# DA1.net
KiCad netlist of a schematic drawn in Altium Designer
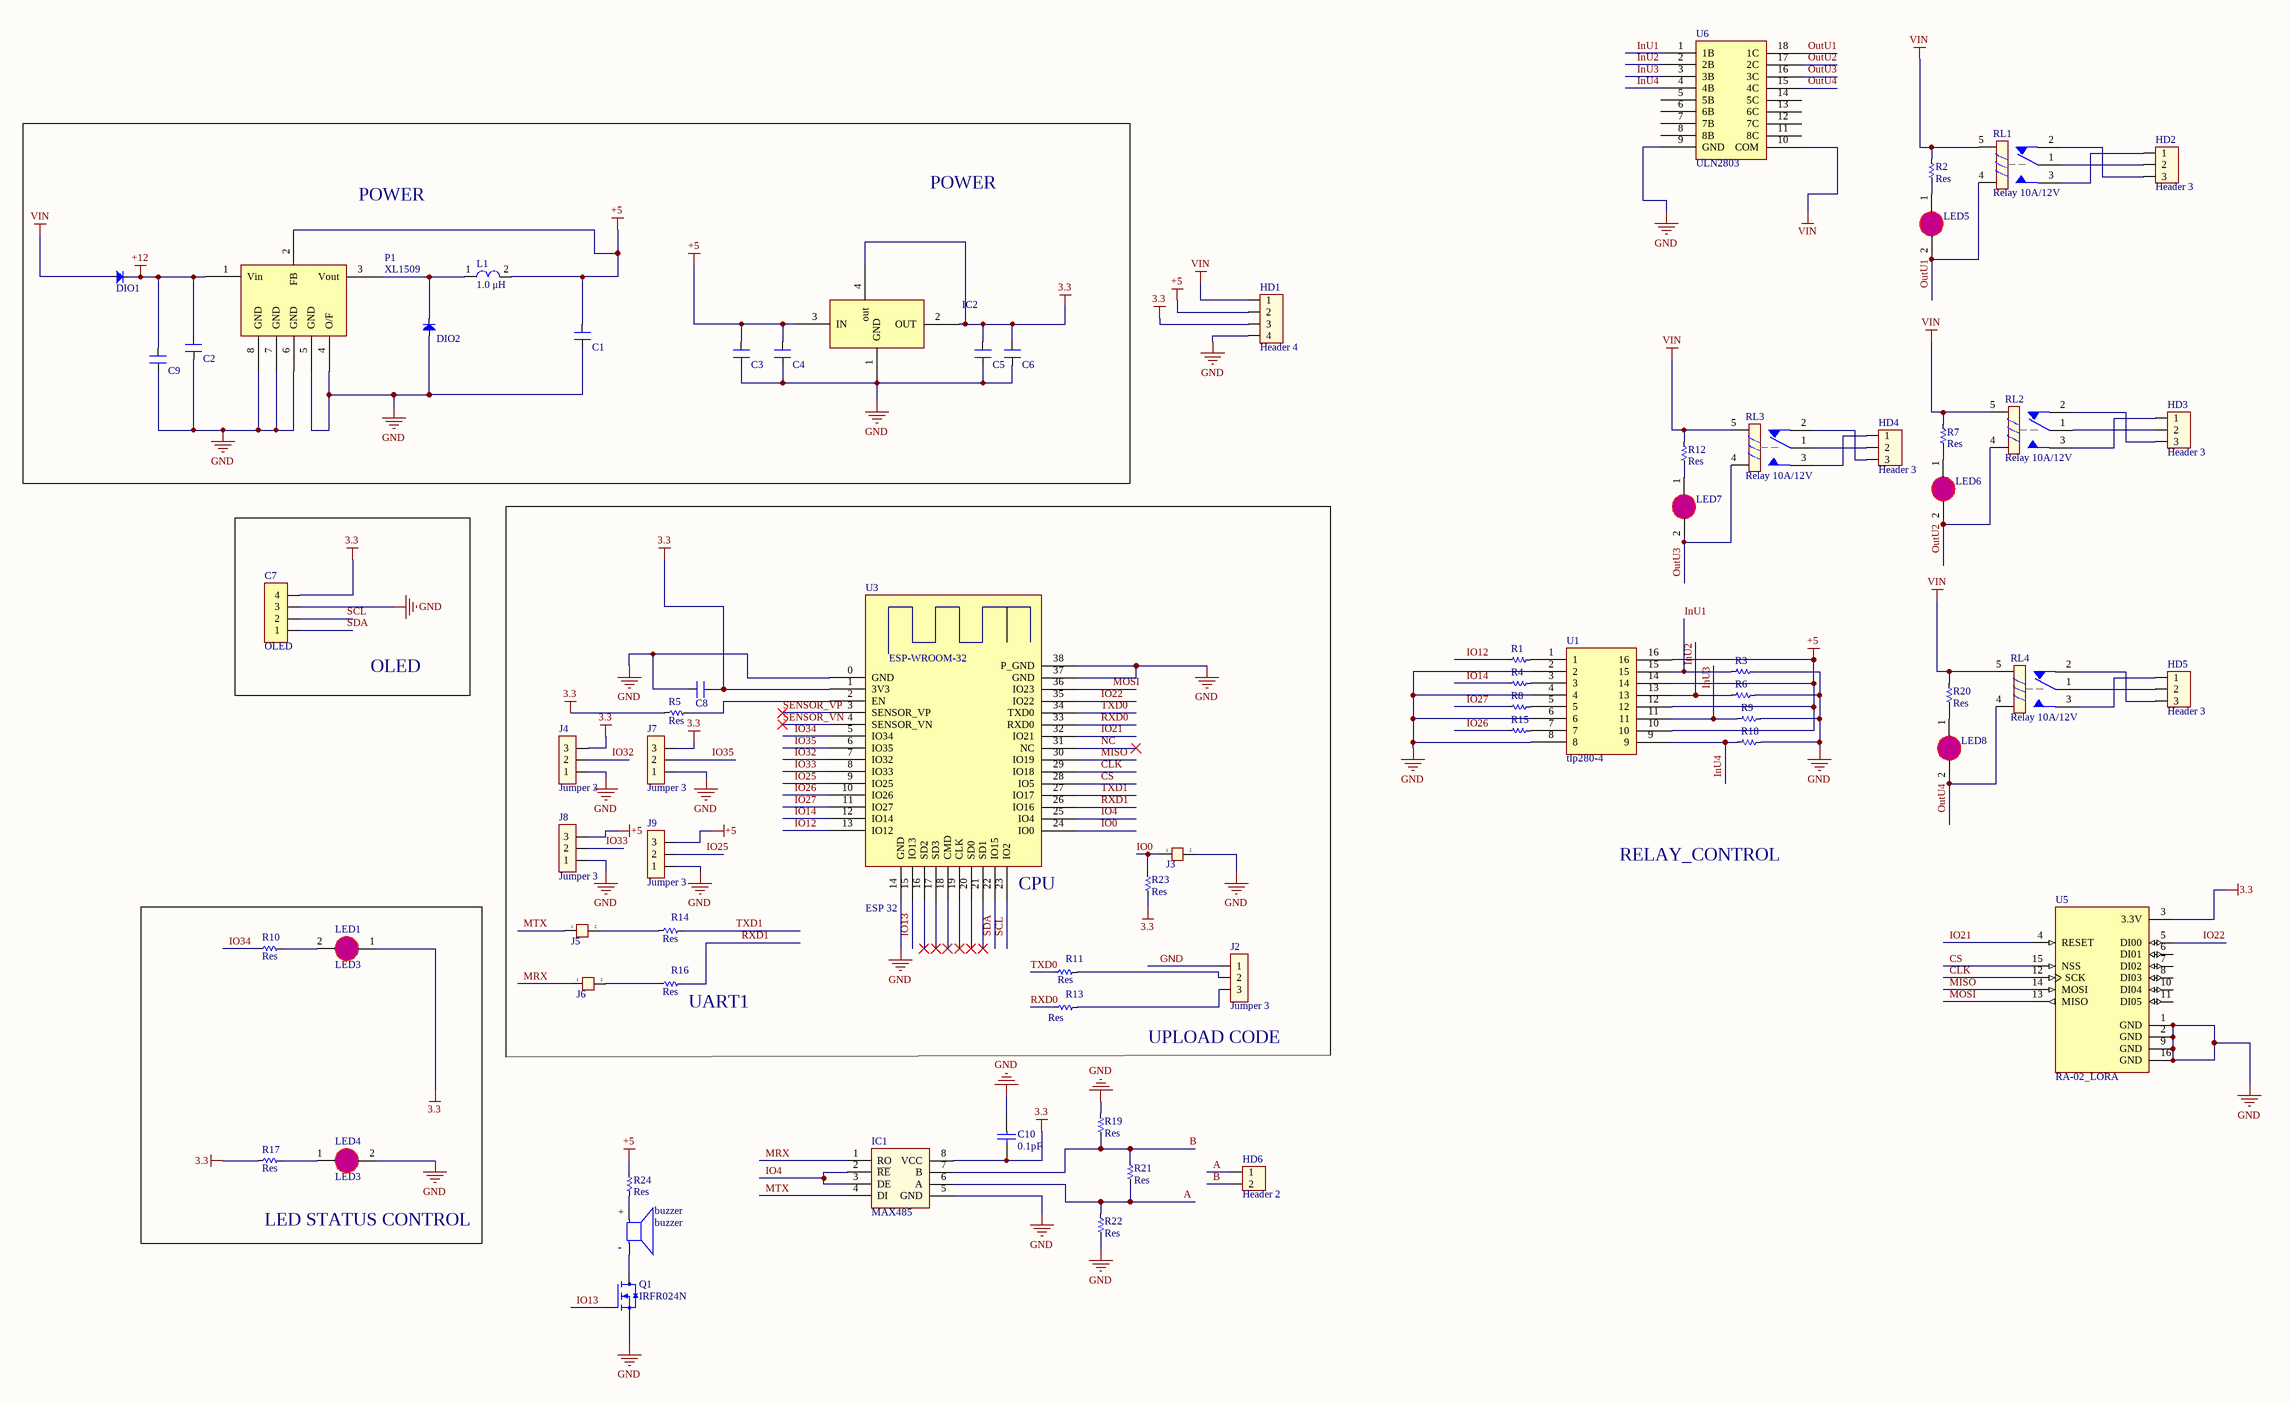
[diagram p0: DA1.SchDoc]

(export (version "E")
  (design (tool "Eeschema 10.0.6"))
  (components
    (comp (ref "buzzer")
      (value "buzzer")
      (footprint "buzzer")
      (description "ELECTRO-MECHANICAL AUDIO INDICATOR")
      (fields (field (name "MP") "AI-1223-TWT-12V-R") (field (name "MF") "PUI Audio,"))
      (libsource (lib "masterq") (part "buzzer"))
    )
    (comp (ref "C1")
      (value "CAPSMD")
      (footprint "1206")
      (description "Cap SMD")
      (libsource (lib "masterq") (part "CAPSMD"))
    )
    (comp (ref "C2")
      (value "CAPSMD")
      (footprint "1206")
      (description "Cap SMD")
      (libsource (lib "masterq") (part "CAPSMD"))
    )
    (comp (ref "C3")
      (value "CAPSMD")
      (footprint "SM-0805")
      (description "Cap SMD")
      (libsource (lib "masterq") (part "CAPSMD"))
    )
    (comp (ref "C4")
      (value "CAPSMD")
      (footprint "SM-0805")
      (description "Cap SMD")
      (libsource (lib "masterq") (part "CAPSMD"))
    )
    (comp (ref "C5")
      (value "CAPSMD")
      (footprint "SM-0805")
      (description "Cap SMD")
      (libsource (lib "masterq") (part "CAPSMD"))
    )
    (comp (ref "C6")
      (value "CAPSMD")
      (footprint "SM-0805")
      (description "Cap SMD")
      (libsource (lib "masterq") (part "CAPSMD"))
    )
    (comp (ref "C7")
      (value "OLED")
      (footprint "JP4-C1T")
      (description "WR-PHD 2.54 mm Angled Socket Header")
      (fields
        (field (name "MANUFACTURER") "Würth Elektronik eiSos GmbH")
        (field (name "PARTNO") "613004143121")
        (field (name "CREATED BY") "Karrer Zheng")
      )
      (libsource (lib "masterq") (part "JP4"))
    )
    (comp (ref "C8")
      (value "CAPSMD")
      (footprint "SM-0805")
      (description "Cap SMD")
      (libsource (lib "masterq") (part "CAPSMD"))
    )
    (comp (ref "C9")
      (value "CAPSMD")
      (footprint "1206")
      (description "Cap SMD")
      (libsource (lib "masterq") (part "CAPSMD"))
    )
    (comp (ref "C10")
      (value "0.1pF")
      (footprint "SMT0603")
      (description "CAP SM 0603 NC")
      (fields (field (name "TOLERANCE") "±10%") (field (name "Comment") "Cap"))
      (libsource (lib "masterq") (part "CAP-SM-0603-NC"))
    )
    (comp (ref "DIO1")
      (value "Diode SMD")
      (footprint "DIO-SMD-106")
      (description "Default Diode")
      (fields (field (name "PUBLISHER") "Altium Limited"))
      (libsource (lib "masterq") (part "Diode SMD"))
    )
    (comp (ref "DIO2")
      (value "Diode SMD")
      (footprint "DIO-SMD-106")
      (description "Default Diode")
      (fields (field (name "PUBLISHER") "Altium Limited"))
      (libsource (lib "masterq") (part "Diode SMD"))
    )
    (comp (ref "HD1")
      (value "Header 4")
      (footprint "HED4T")
      (description "Header 4 (Green)")
      (libsource (lib "masterq") (part "Hed4"))
    )
    (comp (ref "HD2")
      (value "Header 3")
      (footprint "HED3T")
      (description "Header 3 (Green)")
      (libsource (lib "masterq") (part "Hed3"))
    )
    (comp (ref "HD3")
      (value "Header 3")
      (footprint "HED3T")
      (description "Header 3 (Green)")
      (libsource (lib "masterq") (part "Hed3"))
    )
    (comp (ref "HD4")
      (value "Header 3")
      (footprint "HED3T")
      (description "Header 3 (Green)")
      (libsource (lib "masterq") (part "Hed3"))
    )
    (comp (ref "HD5")
      (value "Header 3")
      (footprint "HED3T")
      (description "Header 3 (Green)")
      (libsource (lib "masterq") (part "Hed3"))
    )
    (comp (ref "HD6")
      (value "Header 2")
      (footprint "HED2T")
      (description "Header 2 (Green)")
      (libsource (lib "masterq") (part "Hed2"))
    )
    (comp (ref "IC1")
      (value "MAX485")
      (footprint "SO-8")
      (description "RS232 - RS485 (Same sn75176)")
      (libsource (lib "masterq") (part "MAX485"))
    )
    (comp (ref "IC2")
      (value "ams1117")
      (footprint "SOT223-4N")
      (description "AMS 1117 : output 3.3,5,... (SOT223-4P)")
      (libsource (lib "masterq") (part "ams1117"))
    )
    (comp (ref "J2") (value "Jumper 3") (footprint "JP3") (libsource (lib "masterq") (part "JP3")))
    (comp (ref "J3") (value "Jumper 2") (footprint "J2") (libsource (lib "masterq") (part "JP 2")))
    (comp (ref "J4") (value "Jumper 3") (footprint "JP3") (libsource (lib "") (part "JP3_1")))
    (comp (ref "J5") (value "Jumper 2") (footprint "J2") (libsource (lib "masterq") (part "JP 2")))
    (comp (ref "J6") (value "Jumper 2") (footprint "J2") (libsource (lib "masterq") (part "JP 2")))
    (comp (ref "J7") (value "Jumper 3") (footprint "JP3") (libsource (lib "") (part "JP3_1")))
    (comp (ref "J8") (value "Jumper 3") (footprint "JP3") (libsource (lib "") (part "JP3_1")))
    (comp (ref "J9") (value "Jumper 3") (footprint "JP3") (libsource (lib "") (part "JP3_1")))
    (comp (ref "L1")
      (value "1.0 μH")
      (footprint "L-SMD-M-7.3x4.5")
      (fields
        (field (name "PARTNO") "78477010")
        (field (name "MANUFACTURER") "Wurth Elektronik")
        (field (name "CREATED BY") "Baojun Chen")
      )
      (libsource (lib "masterq") (part "L-SMD-1"))
    )
    (comp (ref "LED1")
      (value "LED3")
      (footprint "LED0805")
      (description "LED 3mm")
      (libsource (lib "masterq") (part "LEDSMD"))
    )
    (comp (ref "LED4")
      (value "LED3")
      (footprint "LED0805")
      (description "LED 3mm")
      (libsource (lib "masterq") (part "LEDSMD"))
    )
    (comp (ref "LED5")
      (value "~")
      (footprint "LED0805")
      (description "LED 3mm")
      (libsource (lib "masterq") (part "LEDSMD"))
    )
    (comp (ref "LED6")
      (value "~")
      (footprint "LED0805")
      (description "LED 3mm")
      (libsource (lib "masterq") (part "LEDSMD"))
    )
    (comp (ref "LED7")
      (value "~")
      (footprint "LED0805")
      (description "LED 3mm")
      (libsource (lib "masterq") (part "LEDSMD"))
    )
    (comp (ref "LED8")
      (value "~")
      (footprint "LED0805")
      (description "LED 3mm")
      (libsource (lib "masterq") (part "LEDSMD"))
    )
    (comp (ref "P1") (value "XL1509") (footprint "SOIC-8") (libsource (lib "masterq") (part "XL1509")))
    (comp (ref "Q1")
      (value "IRFR024N")
      (footprint "FET-SMD")
      (description "N-Channel 55 V 17A (Tc) 45W (Tc) Surface Mount D-Pak")
      (fields (field (name "MF") "Infineon Technologies"))
      (libsource (lib "masterq") (part "IRFR024N"))
    )
    (comp (ref "R1")
      (value "Res")
      (footprint "RES-SMD-0805")
      (description "Resistor")
      (fields
        (field (name "MANUFACTURER") "Generic Components")
        (field (name "PUBLISHER") "Altium Hobart Technology Centre")
      )
      (libsource (lib "masterq") (part "Res-SMD"))
    )
    (comp (ref "R2")
      (value "Res")
      (footprint "RES-SMD-0805")
      (description "Resistor")
      (fields
        (field (name "MANUFACTURER") "Generic Components")
        (field (name "PUBLISHER") "Altium Hobart Technology Centre")
      )
      (libsource (lib "masterq") (part "Res-SMD"))
    )
    (comp (ref "R3")
      (value "Res")
      (footprint "RES-SMD-0805")
      (description "Resistor")
      (fields
        (field (name "MANUFACTURER") "Generic Components")
        (field (name "PUBLISHER") "Altium Hobart Technology Centre")
      )
      (libsource (lib "masterq") (part "Res-SMD"))
    )
    (comp (ref "R4")
      (value "Res")
      (footprint "RES-SMD-0805")
      (description "Resistor")
      (fields
        (field (name "MANUFACTURER") "Generic Components")
        (field (name "PUBLISHER") "Altium Hobart Technology Centre")
      )
      (libsource (lib "masterq") (part "Res-SMD"))
    )
    (comp (ref "R5")
      (value "Res")
      (footprint "RES-SMD-0805")
      (description "Resistor")
      (fields
        (field (name "MANUFACTURER") "Generic Components")
        (field (name "PUBLISHER") "Altium Hobart Technology Centre")
      )
      (libsource (lib "masterq") (part "Res-SMD"))
    )
    (comp (ref "R6")
      (value "Res")
      (footprint "RES-SMD-0805")
      (description "Resistor")
      (fields
        (field (name "MANUFACTURER") "Generic Components")
        (field (name "PUBLISHER") "Altium Hobart Technology Centre")
      )
      (libsource (lib "masterq") (part "Res-SMD"))
    )
    (comp (ref "R7")
      (value "Res")
      (footprint "RES-SMD-0805")
      (description "Resistor")
      (fields
        (field (name "MANUFACTURER") "Generic Components")
        (field (name "PUBLISHER") "Altium Hobart Technology Centre")
      )
      (libsource (lib "masterq") (part "Res-SMD"))
    )
    (comp (ref "R8")
      (value "Res")
      (footprint "RES-SMD-0805")
      (description "Resistor")
      (fields
        (field (name "MANUFACTURER") "Generic Components")
        (field (name "PUBLISHER") "Altium Hobart Technology Centre")
      )
      (libsource (lib "masterq") (part "Res-SMD"))
    )
    (comp (ref "R9")
      (value "Res")
      (footprint "RES-SMD-0805")
      (description "Resistor")
      (fields
        (field (name "MANUFACTURER") "Generic Components")
        (field (name "PUBLISHER") "Altium Hobart Technology Centre")
      )
      (libsource (lib "masterq") (part "Res-SMD"))
    )
    (comp (ref "R10")
      (value "Res")
      (footprint "RES-SMD-0805")
      (description "Resistor")
      (fields
        (field (name "MANUFACTURER") "Generic Components")
        (field (name "PUBLISHER") "Altium Hobart Technology Centre")
      )
      (libsource (lib "masterq") (part "Res-SMD"))
    )
    (comp (ref "R11")
      (value "Res")
      (footprint "RES-SMD-0805")
      (description "Resistor")
      (fields
        (field (name "MANUFACTURER") "Generic Components")
        (field (name "PUBLISHER") "Altium Hobart Technology Centre")
      )
      (libsource (lib "masterq") (part "Res-SMD"))
    )
    (comp (ref "R12")
      (value "Res")
      (footprint "RES-SMD-0805")
      (description "Resistor")
      (fields
        (field (name "MANUFACTURER") "Generic Components")
        (field (name "PUBLISHER") "Altium Hobart Technology Centre")
      )
      (libsource (lib "masterq") (part "Res-SMD"))
    )
    (comp (ref "R13")
      (value "Res")
      (footprint "RES-SMD-0805")
      (description "Resistor")
      (fields
        (field (name "MANUFACTURER") "Generic Components")
        (field (name "PUBLISHER") "Altium Hobart Technology Centre")
      )
      (libsource (lib "masterq") (part "Res-SMD"))
    )
    (comp (ref "R14")
      (value "Res")
      (footprint "RES-SMD-0805")
      (description "Resistor")
      (fields
        (field (name "MANUFACTURER") "Generic Components")
        (field (name "PUBLISHER") "Altium Hobart Technology Centre")
      )
      (libsource (lib "masterq") (part "Res-SMD"))
    )
    (comp (ref "R15")
      (value "Res")
      (footprint "RES-SMD-0805")
      (description "Resistor")
      (fields
        (field (name "MANUFACTURER") "Generic Components")
        (field (name "PUBLISHER") "Altium Hobart Technology Centre")
      )
      (libsource (lib "masterq") (part "Res-SMD"))
    )
    (comp (ref "R16")
      (value "Res")
      (footprint "RES-SMD-0805")
      (description "Resistor")
      (fields
        (field (name "MANUFACTURER") "Generic Components")
        (field (name "PUBLISHER") "Altium Hobart Technology Centre")
      )
      (libsource (lib "masterq") (part "Res-SMD"))
    )
    (comp (ref "R17")
      (value "Res")
      (footprint "RES-SMD-0805")
      (description "Resistor")
      (fields
        (field (name "MANUFACTURER") "Generic Components")
        (field (name "PUBLISHER") "Altium Hobart Technology Centre")
      )
      (libsource (lib "masterq") (part "Res-SMD"))
    )
    (comp (ref "R18")
      (value "Res")
      (footprint "RES-SMD-0805")
      (description "Resistor")
      (fields
        (field (name "MANUFACTURER") "Generic Components")
        (field (name "PUBLISHER") "Altium Hobart Technology Centre")
      )
      (libsource (lib "masterq") (part "Res-SMD"))
    )
    (comp (ref "R19")
      (value "Res")
      (footprint "RES-SMD-0805")
      (description "Resistor")
      (fields
        (field (name "MANUFACTURER") "Generic Components")
        (field (name "PUBLISHER") "Altium Hobart Technology Centre")
      )
      (libsource (lib "masterq") (part "Res-SMD"))
    )
    (comp (ref "R20")
      (value "Res")
      (footprint "RES-SMD-0805")
      (description "Resistor")
      (fields
        (field (name "MANUFACTURER") "Generic Components")
        (field (name "PUBLISHER") "Altium Hobart Technology Centre")
      )
      (libsource (lib "masterq") (part "Res-SMD"))
    )
    (comp (ref "R21")
      (value "Res")
      (footprint "RES-SMD-0805")
      (description "Resistor")
      (fields
        (field (name "MANUFACTURER") "Generic Components")
        (field (name "PUBLISHER") "Altium Hobart Technology Centre")
      )
      (libsource (lib "masterq") (part "Res-SMD"))
    )
    (comp (ref "R22")
      (value "Res")
      (footprint "RES-SMD-0805")
      (description "Resistor")
      (fields
        (field (name "MANUFACTURER") "Generic Components")
        (field (name "PUBLISHER") "Altium Hobart Technology Centre")
      )
      (libsource (lib "masterq") (part "Res-SMD"))
    )
    (comp (ref "R23")
      (value "Res")
      (footprint "RES-SMD-0805")
      (description "Resistor")
      (fields
        (field (name "MANUFACTURER") "Generic Components")
        (field (name "PUBLISHER") "Altium Hobart Technology Centre")
      )
      (libsource (lib "masterq") (part "Res-SMD"))
    )
    (comp (ref "R24")
      (value "Res")
      (footprint "RES-SMD-0805")
      (description "Resistor")
      (fields
        (field (name "MANUFACTURER") "Generic Components")
        (field (name "PUBLISHER") "Altium Hobart Technology Centre")
      )
      (libsource (lib "masterq") (part "Res-SMD"))
    )
    (comp (ref "RL1")
      (value "Relay 10A/12V")
      (footprint "RL_SPDT_10A")
      (description "Relay SPDT,10A - 12VDC 5 Pin")
      (libsource (lib "masterq") (part "Relay 1_1"))
    )
    (comp (ref "RL2")
      (value "Relay 10A/12V")
      (footprint "RL_SPDT_10A")
      (description "Relay SPDT,10A - 12VDC 5 Pin")
      (libsource (lib "masterq") (part "Relay 1_1"))
    )
    (comp (ref "RL3")
      (value "Relay 10A/12V")
      (footprint "RL_SPDT_10A")
      (description "Relay SPDT,10A - 12VDC 5 Pin")
      (libsource (lib "masterq") (part "Relay 1_1"))
    )
    (comp (ref "RL4")
      (value "Relay 10A/12V")
      (footprint "RL_SPDT_10A")
      (description "Relay SPDT,10A - 12VDC 5 Pin")
      (libsource (lib "masterq") (part "Relay 1_1"))
    )
    (comp (ref "U1") (value "tlp280-4") (footprint "SOP16") (libsource (lib "masterq") (part "tlp280-4")))
    (comp (ref "U3") (value "ESP 32") (footprint "ESP 32") (libsource (lib "masterq") (part "ESP 32")))
    (comp (ref "U5")
      (value "RA-02_LORA")
      (footprint "MODULE_RA-02_LORA")
      (description "Ra-02 LoRa RF M5Stack Platform Evaluation Expansion Board")
      (fields (field (name "MP") "Ra-02 LoRa") (field (name "MF") "AI-Thinker"))
      (libsource (lib "masterq") (part "RA-02_LORA"))
    )
    (comp (ref "U6")
      (value "ULN2803")
      (footprint "SOIC 18")
      (description "Darlington Transistor Arrays")
      (libsource (lib "masterq") (part "ULN2803_1"))
    )
  )
  (nets
    (net (code "1") (name "+5") (class "Default")
      (node (ref "C1") (pin "2") (pinfunction "2_2") (pintype "passive"))
      (node (ref "C3") (pin "2") (pinfunction "2_2") (pintype "passive"))
      (node (ref "C4") (pin "2") (pinfunction "2_2") (pintype "passive"))
      (node (ref "HD1") (pin "2") (pinfunction "2_2") (pintype "passive"))
      (node (ref "IC2") (pin "3") (pinfunction "IN_3") (pintype "passive"))
      (node (ref "J8") (pin "3") (pinfunction "3_3") (pintype "passive"))
      (node (ref "J9") (pin "3") (pinfunction "3_3") (pintype "passive"))
      (node (ref "L1") (pin "2") (pinfunction "2_2") (pintype "passive"))
      (node (ref "P1") (pin "2") (pinfunction "FB_2") (pintype "passive"))
      (node (ref "R24") (pin "1") (pinfunction "1_1") (pintype "passive"))
      (node (ref "U1") (pin "10") (pinfunction "10_10") (pintype "passive"))
      (node (ref "U1") (pin "12") (pinfunction "12_12") (pintype "passive"))
      (node (ref "U1") (pin "14") (pinfunction "14_14") (pintype "passive"))
      (node (ref "U1") (pin "16") (pinfunction "16_16") (pintype "passive"))
    )
    (net (code "2") (name "+12") (class "Default")
      (node (ref "C2") (pin "2") (pinfunction "2_2") (pintype "passive"))
      (node (ref "C9") (pin "2") (pinfunction "2_2") (pintype "passive"))
      (node (ref "DIO1") (pin "2") (pinfunction "K_2") (pintype "passive"))
      (node (ref "P1") (pin "1") (pinfunction "Vin_1") (pintype "passive"))
    )
    (net (code "3") (name "/A") (class "Default")
      (node (ref "HD6") (pin "1") (pinfunction "1_1") (pintype "passive"))
      (node (ref "IC1") (pin "6") (pinfunction "A_6") (pintype "passive"))
      (node (ref "R21") (pin "2") (pinfunction "2_2") (pintype "passive"))
      (node (ref "R22") (pin "1") (pinfunction "1_1") (pintype "passive"))
    )
    (net (code "4") (name "/B") (class "Default")
      (node (ref "HD6") (pin "2") (pinfunction "2_2") (pintype "passive"))
      (node (ref "IC1") (pin "7") (pinfunction "B_7") (pintype "passive"))
      (node (ref "R19") (pin "2") (pinfunction "2_2") (pintype "passive"))
      (node (ref "R21") (pin "1") (pinfunction "1_1") (pintype "passive"))
    )
    (net (code "5") (name "/CLK") (class "Default")
      (node (ref "U3") (pin "29") (pinfunction "IO18_29") (pintype "passive"))
      (node (ref "U5") (pin "12") (pinfunction "SCK_12") (pintype "input"))
    )
    (net (code "6") (name "/CS") (class "Default")
      (node (ref "U3") (pin "28") (pinfunction "IO5_28") (pintype "passive"))
      (node (ref "U5") (pin "15") (pinfunction "NSS_15") (pintype "input"))
    )
    (net (code "7") (name "/IO0") (class "Default")
      (node (ref "J3") (pin "1") (pinfunction "1_1") (pintype "passive"))
      (node (ref "R23") (pin "1") (pinfunction "1_1") (pintype "passive"))
      (node (ref "U3") (pin "24") (pinfunction "IO0_24") (pintype "passive"))
    )
    (net (code "8") (name "/IO4") (class "Default")
      (node (ref "IC1") (pin "2") (pinfunction "~{RE}_2") (pintype "passive"))
      (node (ref "IC1") (pin "3") (pinfunction "DE_3") (pintype "passive"))
      (node (ref "U3") (pin "25") (pinfunction "IO4_25") (pintype "passive"))
    )
    (net (code "9") (name "/IO12") (class "Default")
      (node (ref "R1") (pin "1") (pinfunction "1_1") (pintype "passive"))
      (node (ref "U3") (pin "13") (pinfunction "IO12_13") (pintype "passive"))
    )
    (net (code "10") (name "/IO13") (class "Default")
      (node (ref "Q1") (pin "1") (pinfunction "G_1") (pintype "passive"))
      (node (ref "U3") (pin "15") (pinfunction "IO13_15") (pintype "passive"))
    )
    (net (code "11") (name "/IO14") (class "Default")
      (node (ref "R4") (pin "1") (pinfunction "1_1") (pintype "passive"))
      (node (ref "U3") (pin "12") (pinfunction "IO14_12") (pintype "passive"))
    )
    (net (code "12") (name "/IO21") (class "Default")
      (node (ref "U3") (pin "32") (pinfunction "IO21_32") (pintype "passive"))
      (node (ref "U5") (pin "4") (pinfunction "RESET_4") (pintype "input"))
    )
    (net (code "13") (name "/IO22") (class "Default")
      (node (ref "U3") (pin "35") (pinfunction "IO22_35") (pintype "passive"))
      (node (ref "U5") (pin "5") (pinfunction "DI00_5") (pintype "bidirectional"))
    )
    (net (code "14") (name "/IO25") (class "Default")
      (node (ref "J9") (pin "2") (pinfunction "2_2") (pintype "passive"))
      (node (ref "U3") (pin "9") (pinfunction "IO25_9") (pintype "passive"))
    )
    (net (code "15") (name "/IO26") (class "Default")
      (node (ref "R15") (pin "1") (pinfunction "1_1") (pintype "passive"))
      (node (ref "U3") (pin "10") (pinfunction "IO26_10") (pintype "passive"))
    )
    (net (code "16") (name "/IO27") (class "Default")
      (node (ref "R8") (pin "1") (pinfunction "1_1") (pintype "passive"))
      (node (ref "U3") (pin "11") (pinfunction "IO27_11") (pintype "passive"))
    )
    (net (code "17") (name "/IO32") (class "Default")
      (node (ref "J4") (pin "2") (pinfunction "2_2") (pintype "passive"))
      (node (ref "U3") (pin "7") (pinfunction "IO32_7") (pintype "passive"))
    )
    (net (code "18") (name "/IO33") (class "Default")
      (node (ref "J8") (pin "2") (pinfunction "2_2") (pintype "passive"))
      (node (ref "U3") (pin "8") (pinfunction "IO33_8") (pintype "passive"))
    )
    (net (code "19") (name "/IO34") (class "Default")
      (node (ref "R10") (pin "2") (pinfunction "2_2") (pintype "passive"))
      (node (ref "U3") (pin "5") (pinfunction "IO34_5") (pintype "passive"))
    )
    (net (code "20") (name "/IO35") (class "Default")
      (node (ref "J7") (pin "2") (pinfunction "2_2") (pintype "passive"))
      (node (ref "U3") (pin "6") (pinfunction "IO35_6") (pintype "passive"))
    )
    (net (code "21") (name "/InU1") (class "Default")
      (node (ref "R3") (pin "1") (pinfunction "1_1") (pintype "passive"))
      (node (ref "U1") (pin "15") (pinfunction "15_15") (pintype "passive"))
      (node (ref "U6") (pin "1") (pinfunction "1B_1") (pintype "passive"))
    )
    (net (code "22") (name "/InU2") (class "Default")
      (node (ref "R6") (pin "1") (pinfunction "1_1") (pintype "passive"))
      (node (ref "U1") (pin "13") (pinfunction "13_13") (pintype "passive"))
      (node (ref "U6") (pin "2") (pinfunction "2B_2") (pintype "passive"))
    )
    (net (code "23") (name "/InU3") (class "Default")
      (node (ref "R9") (pin "1") (pinfunction "1_1") (pintype "passive"))
      (node (ref "U1") (pin "11") (pinfunction "11_11") (pintype "passive"))
      (node (ref "U6") (pin "3") (pinfunction "3B_3") (pintype "passive"))
    )
    (net (code "24") (name "/InU4") (class "Default")
      (node (ref "R18") (pin "1") (pinfunction "1_1") (pintype "passive"))
      (node (ref "U1") (pin "9") (pinfunction "9_9") (pintype "passive"))
      (node (ref "U6") (pin "4") (pinfunction "4B_4") (pintype "passive"))
    )
    (net (code "25") (name "/MISO") (class "Default")
      (node (ref "U3") (pin "30") (pinfunction "IO19_30") (pintype "passive"))
      (node (ref "U5") (pin "14") (pinfunction "MOSI_14") (pintype "input"))
    )
    (net (code "26") (name "/MOSI") (class "Default")
      (node (ref "U3") (pin "36") (pinfunction "IO23_36") (pintype "passive"))
      (node (ref "U5") (pin "13") (pinfunction "MISO_13") (pintype "output"))
    )
    (net (code "27") (name "/MRX") (class "Default")
      (node (ref "IC1") (pin "1") (pinfunction "RO_1") (pintype "passive"))
      (node (ref "J6") (pin "1") (pinfunction "1_1") (pintype "passive"))
    )
    (net (code "28") (name "/MTX") (class "Default")
      (node (ref "IC1") (pin "4") (pinfunction "DI_4") (pintype "passive"))
      (node (ref "J5") (pin "1") (pinfunction "1_1") (pintype "passive"))
    )
    (net (code "29") (name "/NC") (class "Default")
      (node (ref "U3") (pin "31") (pinfunction "NC_31") (pintype "passive+no_connect"))
    )
    (net (code "30") (name "/OutU1") (class "Default")
      (node (ref "LED5") (pin "2") (pinfunction "K_2") (pintype "passive"))
      (node (ref "RL1") (pin "4") (pinfunction "4_4") (pintype "passive"))
      (node (ref "U6") (pin "18") (pinfunction "1C_18") (pintype "passive"))
    )
    (net (code "31") (name "/OutU2") (class "Default")
      (node (ref "LED6") (pin "2") (pinfunction "K_2") (pintype "passive"))
      (node (ref "RL2") (pin "4") (pinfunction "4_4") (pintype "passive"))
      (node (ref "U6") (pin "17") (pinfunction "2C_17") (pintype "passive"))
    )
    (net (code "32") (name "/OutU3") (class "Default")
      (node (ref "LED7") (pin "2") (pinfunction "K_2") (pintype "passive"))
      (node (ref "RL3") (pin "4") (pinfunction "4_4") (pintype "passive"))
      (node (ref "U6") (pin "16") (pinfunction "3C_16") (pintype "passive"))
    )
    (net (code "33") (name "/OutU4") (class "Default")
      (node (ref "LED8") (pin "2") (pinfunction "K_2") (pintype "passive"))
      (node (ref "RL4") (pin "4") (pinfunction "4_4") (pintype "passive"))
      (node (ref "U6") (pin "15") (pinfunction "4C_15") (pintype "passive"))
    )
    (net (code "34") (name "/RXD0") (class "Default")
      (node (ref "R13") (pin "2") (pinfunction "2_2") (pintype "passive"))
      (node (ref "U3") (pin "33") (pinfunction "RXD0_33") (pintype "passive"))
    )
    (net (code "35") (name "/RXD1") (class "Default")
      (node (ref "R16") (pin "1") (pinfunction "1_1") (pintype "passive"))
      (node (ref "U3") (pin "26") (pinfunction "IO16_26") (pintype "passive"))
    )
    (net (code "36") (name "/SCL") (class "Default")
      (node (ref "C7") (pin "2") (pinfunction "2_2") (pintype "passive"))
      (node (ref "U3") (pin "23") (pinfunction "IO2_23") (pintype "passive"))
    )
    (net (code "37") (name "/SDA") (class "Default")
      (node (ref "C7") (pin "1") (pinfunction "1_1") (pintype "passive"))
      (node (ref "U3") (pin "22") (pinfunction "IO15_22") (pintype "passive"))
    )
    (net (code "38") (name "/SENSOR_VN") (class "Default")
      (node (ref "U3") (pin "4") (pinfunction "SENSOR_VN_4") (pintype "passive+no_connect"))
    )
    (net (code "39") (name "/SENSOR_VP") (class "Default")
      (node (ref "U3") (pin "3") (pinfunction "SENSOR_VP_3") (pintype "passive+no_connect"))
    )
    (net (code "40") (name "/TXD0") (class "Default")
      (node (ref "R11") (pin "2") (pinfunction "2_2") (pintype "passive"))
      (node (ref "U3") (pin "34") (pinfunction "TXD0_34") (pintype "passive"))
    )
    (net (code "41") (name "/TXD1") (class "Default")
      (node (ref "R14") (pin "1") (pinfunction "1_1") (pintype "passive"))
      (node (ref "U3") (pin "27") (pinfunction "IO17_27") (pintype "passive"))
    )
    (net (code "42") (name "3.3") (class "Default")
      (node (ref "C10") (pin "1") (pinfunction "1_1") (pintype "passive"))
      (node (ref "C5") (pin "2") (pinfunction "2_2") (pintype "passive"))
      (node (ref "C6") (pin "2") (pinfunction "2_2") (pintype "passive"))
      (node (ref "C7") (pin "4") (pinfunction "4_4") (pintype "passive"))
      (node (ref "C8") (pin "2") (pinfunction "2_2") (pintype "passive"))
      (node (ref "HD1") (pin "3") (pinfunction "3_3") (pintype "passive"))
      (node (ref "IC1") (pin "8") (pinfunction "VCC_8") (pintype "passive"))
      (node (ref "IC2") (pin "2") (pinfunction "OUT_2") (pintype "passive"))
      (node (ref "IC2") (pin "4") (pinfunction "out_4") (pintype "passive"))
      (node (ref "J4") (pin "3") (pinfunction "3_3") (pintype "passive"))
      (node (ref "J7") (pin "3") (pinfunction "3_3") (pintype "passive"))
      (node (ref "LED1") (pin "1") (pinfunction "A_1") (pintype "passive"))
      (node (ref "R17") (pin "2") (pinfunction "2_2") (pintype "passive"))
      (node (ref "R23") (pin "2") (pinfunction "2_2") (pintype "passive"))
      (node (ref "R5") (pin "2") (pinfunction "2_2") (pintype "passive"))
      (node (ref "U3") (pin "1") (pinfunction "3V3_1") (pintype "passive"))
      (node (ref "U5") (pin "3") (pinfunction "3.3V_3") (pintype "power_in"))
    )
    (net (code "43") (name "GND") (class "Default")
      (node (ref "C1") (pin "1") (pinfunction "1_1") (pintype "passive"))
      (node (ref "C10") (pin "2") (pinfunction "2_2") (pintype "passive"))
      (node (ref "C2") (pin "1") (pinfunction "1_1") (pintype "passive"))
      (node (ref "C3") (pin "1") (pinfunction "1_1") (pintype "passive"))
      (node (ref "C4") (pin "1") (pinfunction "1_1") (pintype "passive"))
      (node (ref "C5") (pin "1") (pinfunction "1_1") (pintype "passive"))
      (node (ref "C6") (pin "1") (pinfunction "1_1") (pintype "passive"))
      (node (ref "C7") (pin "3") (pinfunction "3_3") (pintype "passive"))
      (node (ref "C8") (pin "1") (pinfunction "1_1") (pintype "passive"))
      (node (ref "C9") (pin "1") (pinfunction "1_1") (pintype "passive"))
      (node (ref "DIO2") (pin "1") (pinfunction "A_1") (pintype "passive"))
      (node (ref "HD1") (pin "4") (pinfunction "4_4") (pintype "passive"))
      (node (ref "IC1") (pin "5") (pinfunction "GND_5") (pintype "passive"))
      (node (ref "IC2") (pin "1") (pinfunction "GND_1") (pintype "passive"))
      (node (ref "J2") (pin "1") (pinfunction "1_1") (pintype "passive"))
      (node (ref "J3") (pin "2") (pinfunction "2_2") (pintype "passive"))
      (node (ref "J4") (pin "1") (pinfunction "1_1") (pintype "passive"))
      (node (ref "J7") (pin "1") (pinfunction "1_1") (pintype "passive"))
      (node (ref "J8") (pin "1") (pinfunction "1_1") (pintype "passive"))
      (node (ref "J9") (pin "1") (pinfunction "1_1") (pintype "passive"))
      (node (ref "LED4") (pin "2") (pinfunction "K_2") (pintype "passive"))
      (node (ref "P1") (pin "4") (pinfunction "O/F_4") (pintype "passive"))
      (node (ref "P1") (pin "5") (pinfunction "GND_5") (pintype "passive"))
      (node (ref "P1") (pin "6") (pinfunction "GND_6") (pintype "passive"))
      (node (ref "P1") (pin "7") (pinfunction "GND_7") (pintype "passive"))
      (node (ref "P1") (pin "8") (pinfunction "GND_8") (pintype "passive"))
      (node (ref "Q1") (pin "3") (pinfunction "S_3") (pintype "passive"))
      (node (ref "R18") (pin "2") (pinfunction "2_2") (pintype "passive"))
      (node (ref "R19") (pin "1") (pinfunction "1_1") (pintype "passive"))
      (node (ref "R22") (pin "2") (pinfunction "2_2") (pintype "passive"))
      (node (ref "R3") (pin "2") (pinfunction "2_2") (pintype "passive"))
      (node (ref "R6") (pin "2") (pinfunction "2_2") (pintype "passive"))
      (node (ref "R9") (pin "2") (pinfunction "2_2") (pintype "passive"))
      (node (ref "U1") (pin "2") (pinfunction "2_2") (pintype "passive"))
      (node (ref "U1") (pin "4") (pinfunction "4_4") (pintype "passive"))
      (node (ref "U1") (pin "6") (pinfunction "6_6") (pintype "passive"))
      (node (ref "U1") (pin "8") (pinfunction "8_8") (pintype "passive"))
      (node (ref "U3") (pin "0") (pinfunction "GND_0") (pintype "passive"))
      (node (ref "U3") (pin "14") (pinfunction "GND_14") (pintype "passive"))
      (node (ref "U3") (pin "37") (pinfunction "GND_37") (pintype "passive"))
      (node (ref "U3") (pin "38") (pinfunction "P_GND_38") (pintype "passive"))
      (node (ref "U5") (pin "1") (pinfunction "GND_1") (pintype "power_in"))
      (node (ref "U5") (pin "16") (pinfunction "GND_16") (pintype "power_in"))
      (node (ref "U5") (pin "2") (pinfunction "GND_2") (pintype "power_in"))
      (node (ref "U5") (pin "9") (pinfunction "GND_9") (pintype "power_in"))
      (node (ref "U6") (pin "9") (pinfunction "GND_9") (pintype "passive"))
    )
    (net (code "44") (name "Net-(DIO2-K)") (class "Default")
      (node (ref "DIO2") (pin "2") (pinfunction "K_2") (pintype "passive"))
      (node (ref "L1") (pin "1") (pinfunction "1_1") (pintype "passive"))
      (node (ref "P1") (pin "3") (pinfunction "Vout_3") (pintype "passive"))
    )
    (net (code "45") (name "Net-(HD2-Pad1)") (class "Default")
      (node (ref "HD2") (pin "1") (pinfunction "1_1") (pintype "passive"))
      (node (ref "RL1") (pin "3") (pinfunction "3_3") (pintype "passive"))
    )
    (net (code "46") (name "Net-(HD2-Pad2)") (class "Default")
      (node (ref "HD2") (pin "2") (pinfunction "2_2") (pintype "passive"))
      (node (ref "RL1") (pin "1") (pinfunction "1_1") (pintype "passive"))
    )
    (net (code "47") (name "Net-(HD2-Pad3)") (class "Default")
      (node (ref "HD2") (pin "3") (pinfunction "3_3") (pintype "passive"))
      (node (ref "RL1") (pin "2") (pinfunction "2_2") (pintype "passive"))
    )
    (net (code "48") (name "Net-(HD3-Pad1)") (class "Default")
      (node (ref "HD3") (pin "1") (pinfunction "1_1") (pintype "passive"))
      (node (ref "RL2") (pin "3") (pinfunction "3_3") (pintype "passive"))
    )
    (net (code "49") (name "Net-(HD3-Pad2)") (class "Default")
      (node (ref "HD3") (pin "2") (pinfunction "2_2") (pintype "passive"))
      (node (ref "RL2") (pin "1") (pinfunction "1_1") (pintype "passive"))
    )
    (net (code "50") (name "Net-(HD3-Pad3)") (class "Default")
      (node (ref "HD3") (pin "3") (pinfunction "3_3") (pintype "passive"))
      (node (ref "RL2") (pin "2") (pinfunction "2_2") (pintype "passive"))
    )
    (net (code "51") (name "Net-(HD4-Pad1)") (class "Default")
      (node (ref "HD4") (pin "1") (pinfunction "1_1") (pintype "passive"))
      (node (ref "RL3") (pin "3") (pinfunction "3_3") (pintype "passive"))
    )
    (net (code "52") (name "Net-(HD4-Pad2)") (class "Default")
      (node (ref "HD4") (pin "2") (pinfunction "2_2") (pintype "passive"))
      (node (ref "RL3") (pin "1") (pinfunction "1_1") (pintype "passive"))
    )
    (net (code "53") (name "Net-(HD4-Pad3)") (class "Default")
      (node (ref "HD4") (pin "3") (pinfunction "3_3") (pintype "passive"))
      (node (ref "RL3") (pin "2") (pinfunction "2_2") (pintype "passive"))
    )
    (net (code "54") (name "Net-(HD5-Pad1)") (class "Default")
      (node (ref "HD5") (pin "1") (pinfunction "1_1") (pintype "passive"))
      (node (ref "RL4") (pin "3") (pinfunction "3_3") (pintype "passive"))
    )
    (net (code "55") (name "Net-(HD5-Pad2)") (class "Default")
      (node (ref "HD5") (pin "2") (pinfunction "2_2") (pintype "passive"))
      (node (ref "RL4") (pin "1") (pinfunction "1_1") (pintype "passive"))
    )
    (net (code "56") (name "Net-(HD5-Pad3)") (class "Default")
      (node (ref "HD5") (pin "3") (pinfunction "3_3") (pintype "passive"))
      (node (ref "RL4") (pin "2") (pinfunction "2_2") (pintype "passive"))
    )
    (net (code "57") (name "Net-(J2-Pad2)") (class "Default")
      (node (ref "J2") (pin "2") (pinfunction "2_2") (pintype "passive"))
      (node (ref "R11") (pin "1") (pinfunction "1_1") (pintype "passive"))
    )
    (net (code "58") (name "Net-(J2-Pad3)") (class "Default")
      (node (ref "J2") (pin "3") (pinfunction "3_3") (pintype "passive"))
      (node (ref "R13") (pin "1") (pinfunction "1_1") (pintype "passive"))
    )
    (net (code "59") (name "Net-(J5-Pad2)") (class "Default")
      (node (ref "J5") (pin "2") (pinfunction "2_2") (pintype "passive"))
      (node (ref "R14") (pin "2") (pinfunction "2_2") (pintype "passive"))
    )
    (net (code "60") (name "Net-(J6-Pad2)") (class "Default")
      (node (ref "J6") (pin "2") (pinfunction "2_2") (pintype "passive"))
      (node (ref "R16") (pin "2") (pinfunction "2_2") (pintype "passive"))
    )
    (net (code "61") (name "Net-(LED1-K)") (class "Default")
      (node (ref "LED1") (pin "2") (pinfunction "K_2") (pintype "passive"))
      (node (ref "R10") (pin "1") (pinfunction "1_1") (pintype "passive"))
    )
    (net (code "62") (name "Net-(LED4-A)") (class "Default")
      (node (ref "LED4") (pin "1") (pinfunction "A_1") (pintype "passive"))
      (node (ref "R17") (pin "1") (pinfunction "1_1") (pintype "passive"))
    )
    (net (code "63") (name "Net-(LED5-A)") (class "Default")
      (node (ref "LED5") (pin "1") (pinfunction "A_1") (pintype "passive"))
      (node (ref "R2") (pin "2") (pinfunction "2_2") (pintype "passive"))
    )
    (net (code "64") (name "Net-(LED6-A)") (class "Default")
      (node (ref "LED6") (pin "1") (pinfunction "A_1") (pintype "passive"))
      (node (ref "R7") (pin "2") (pinfunction "2_2") (pintype "passive"))
    )
    (net (code "65") (name "Net-(LED7-A)") (class "Default")
      (node (ref "LED7") (pin "1") (pinfunction "A_1") (pintype "passive"))
      (node (ref "R12") (pin "2") (pinfunction "2_2") (pintype "passive"))
    )
    (net (code "66") (name "Net-(LED8-A)") (class "Default")
      (node (ref "LED8") (pin "1") (pinfunction "A_1") (pintype "passive"))
      (node (ref "R20") (pin "2") (pinfunction "2_2") (pintype "passive"))
    )
    (net (code "67") (name "Net-(Q1-D)") (class "Default")
      (node (ref "Q1") (pin "4") (pinfunction "D_4") (pintype "passive"))
      (node (ref "buzzer") (pin "N") (pinfunction "NEG_N") (pintype "passive"))
    )
    (net (code "68") (name "Net-(R1-Pad2)") (class "Default")
      (node (ref "R1") (pin "2") (pinfunction "2_2") (pintype "passive"))
      (node (ref "U1") (pin "1") (pinfunction "1_1") (pintype "passive"))
    )
    (net (code "69") (name "Net-(R4-Pad2)") (class "Default")
      (node (ref "R4") (pin "2") (pinfunction "2_2") (pintype "passive"))
      (node (ref "U1") (pin "3") (pinfunction "3_3") (pintype "passive"))
    )
    (net (code "70") (name "Net-(R8-Pad2)") (class "Default")
      (node (ref "R8") (pin "2") (pinfunction "2_2") (pintype "passive"))
      (node (ref "U1") (pin "5") (pinfunction "5_5") (pintype "passive"))
    )
    (net (code "71") (name "Net-(R15-Pad2)") (class "Default")
      (node (ref "R15") (pin "2") (pinfunction "2_2") (pintype "passive"))
      (node (ref "U1") (pin "7") (pinfunction "7_7") (pintype "passive"))
    )
    (net (code "72") (name "Net-(U3-EN)") (class "Default")
      (node (ref "R5") (pin "1") (pinfunction "1_1") (pintype "passive"))
      (node (ref "U3") (pin "2") (pinfunction "EN_2") (pintype "passive"))
    )
    (net (code "73") (name "Net-(buzzer-POS)") (class "Default")
      (node (ref "R24") (pin "2") (pinfunction "2_2") (pintype "passive"))
      (node (ref "buzzer") (pin "P") (pinfunction "POS_P") (pintype "passive"))
    )
    (net (code "74") (name "VIN") (class "Default")
      (node (ref "DIO1") (pin "1") (pinfunction "A_1") (pintype "passive"))
      (node (ref "HD1") (pin "1") (pinfunction "1_1") (pintype "passive"))
      (node (ref "R12") (pin "1") (pinfunction "1_1") (pintype "passive"))
      (node (ref "R2") (pin "1") (pinfunction "1_1") (pintype "passive"))
      (node (ref "R20") (pin "1") (pinfunction "1_1") (pintype "passive"))
      (node (ref "R7") (pin "1") (pinfunction "1_1") (pintype "passive"))
      (node (ref "RL1") (pin "5") (pinfunction "5_5") (pintype "passive"))
      (node (ref "RL2") (pin "5") (pinfunction "5_5") (pintype "passive"))
      (node (ref "RL3") (pin "5") (pinfunction "5_5") (pintype "passive"))
      (node (ref "RL4") (pin "5") (pinfunction "5_5") (pintype "passive"))
      (node (ref "U6") (pin "10") (pinfunction "COM_10") (pintype "passive"))
    )
    (net (code "75") (name "unconnected-(U3-CLK-Pad19)") (class "Default")
      (node (ref "U3") (pin "19") (pinfunction "CLK_19") (pintype "passive+no_connect"))
    )
    (net (code "76") (name "unconnected-(U3-CMD-Pad18)") (class "Default")
      (node (ref "U3") (pin "18") (pinfunction "CMD_18") (pintype "passive+no_connect"))
    )
    (net (code "77") (name "unconnected-(U3-SD0-Pad20)") (class "Default")
      (node (ref "U3") (pin "20") (pinfunction "SD0_20") (pintype "passive+no_connect"))
    )
    (net (code "78") (name "unconnected-(U3-SD1-Pad21)") (class "Default")
      (node (ref "U3") (pin "21") (pinfunction "SD1_21") (pintype "passive+no_connect"))
    )
    (net (code "79") (name "unconnected-(U3-SD2-Pad16)") (class "Default")
      (node (ref "U3") (pin "16") (pinfunction "SD2_16") (pintype "passive+no_connect"))
    )
    (net (code "80") (name "unconnected-(U3-SD3-Pad17)") (class "Default")
      (node (ref "U3") (pin "17") (pinfunction "SD3_17") (pintype "passive+no_connect"))
    )
    (net (code "81") (name "unconnected-(U5-DI01-Pad6)") (class "Default")
      (node (ref "U5") (pin "6") (pinfunction "DI01_6") (pintype "bidirectional"))
    )
    (net (code "82") (name "unconnected-(U5-DI02-Pad7)") (class "Default")
      (node (ref "U5") (pin "7") (pinfunction "DI02_7") (pintype "bidirectional"))
    )
    (net (code "83") (name "unconnected-(U5-DI03-Pad8)") (class "Default")
      (node (ref "U5") (pin "8") (pinfunction "DI03_8") (pintype "bidirectional"))
    )
    (net (code "84") (name "unconnected-(U5-DI04-Pad10)") (class "Default")
      (node (ref "U5") (pin "10") (pinfunction "DI04_10") (pintype "bidirectional"))
    )
    (net (code "85") (name "unconnected-(U5-DI05-Pad11)") (class "Default")
      (node (ref "U5") (pin "11") (pinfunction "DI05_11") (pintype "bidirectional"))
    )
    (net (code "86") (name "unconnected-(U6-5B-Pad5)") (class "Default")
      (node (ref "U6") (pin "5") (pinfunction "5B_5") (pintype "passive"))
    )
    (net (code "87") (name "unconnected-(U6-5C-Pad14)") (class "Default")
      (node (ref "U6") (pin "14") (pinfunction "5C_14") (pintype "passive"))
    )
    (net (code "88") (name "unconnected-(U6-6B-Pad6)") (class "Default")
      (node (ref "U6") (pin "6") (pinfunction "6B_6") (pintype "passive"))
    )
    (net (code "89") (name "unconnected-(U6-6C-Pad13)") (class "Default")
      (node (ref "U6") (pin "13") (pinfunction "6C_13") (pintype "passive"))
    )
    (net (code "90") (name "unconnected-(U6-7B-Pad7)") (class "Default")
      (node (ref "U6") (pin "7") (pinfunction "7B_7") (pintype "passive"))
    )
    (net (code "91") (name "unconnected-(U6-7C-Pad12)") (class "Default")
      (node (ref "U6") (pin "12") (pinfunction "7C_12") (pintype "passive"))
    )
    (net (code "92") (name "unconnected-(U6-8B-Pad8)") (class "Default")
      (node (ref "U6") (pin "8") (pinfunction "8B_8") (pintype "passive"))
    )
    (net (code "93") (name "unconnected-(U6-8C-Pad11)") (class "Default")
      (node (ref "U6") (pin "11") (pinfunction "8C_11") (pintype "passive"))
    )
  )
)
